# EsquemaPWM.net
KiCad netlist of a schematic drawn in EAGLE
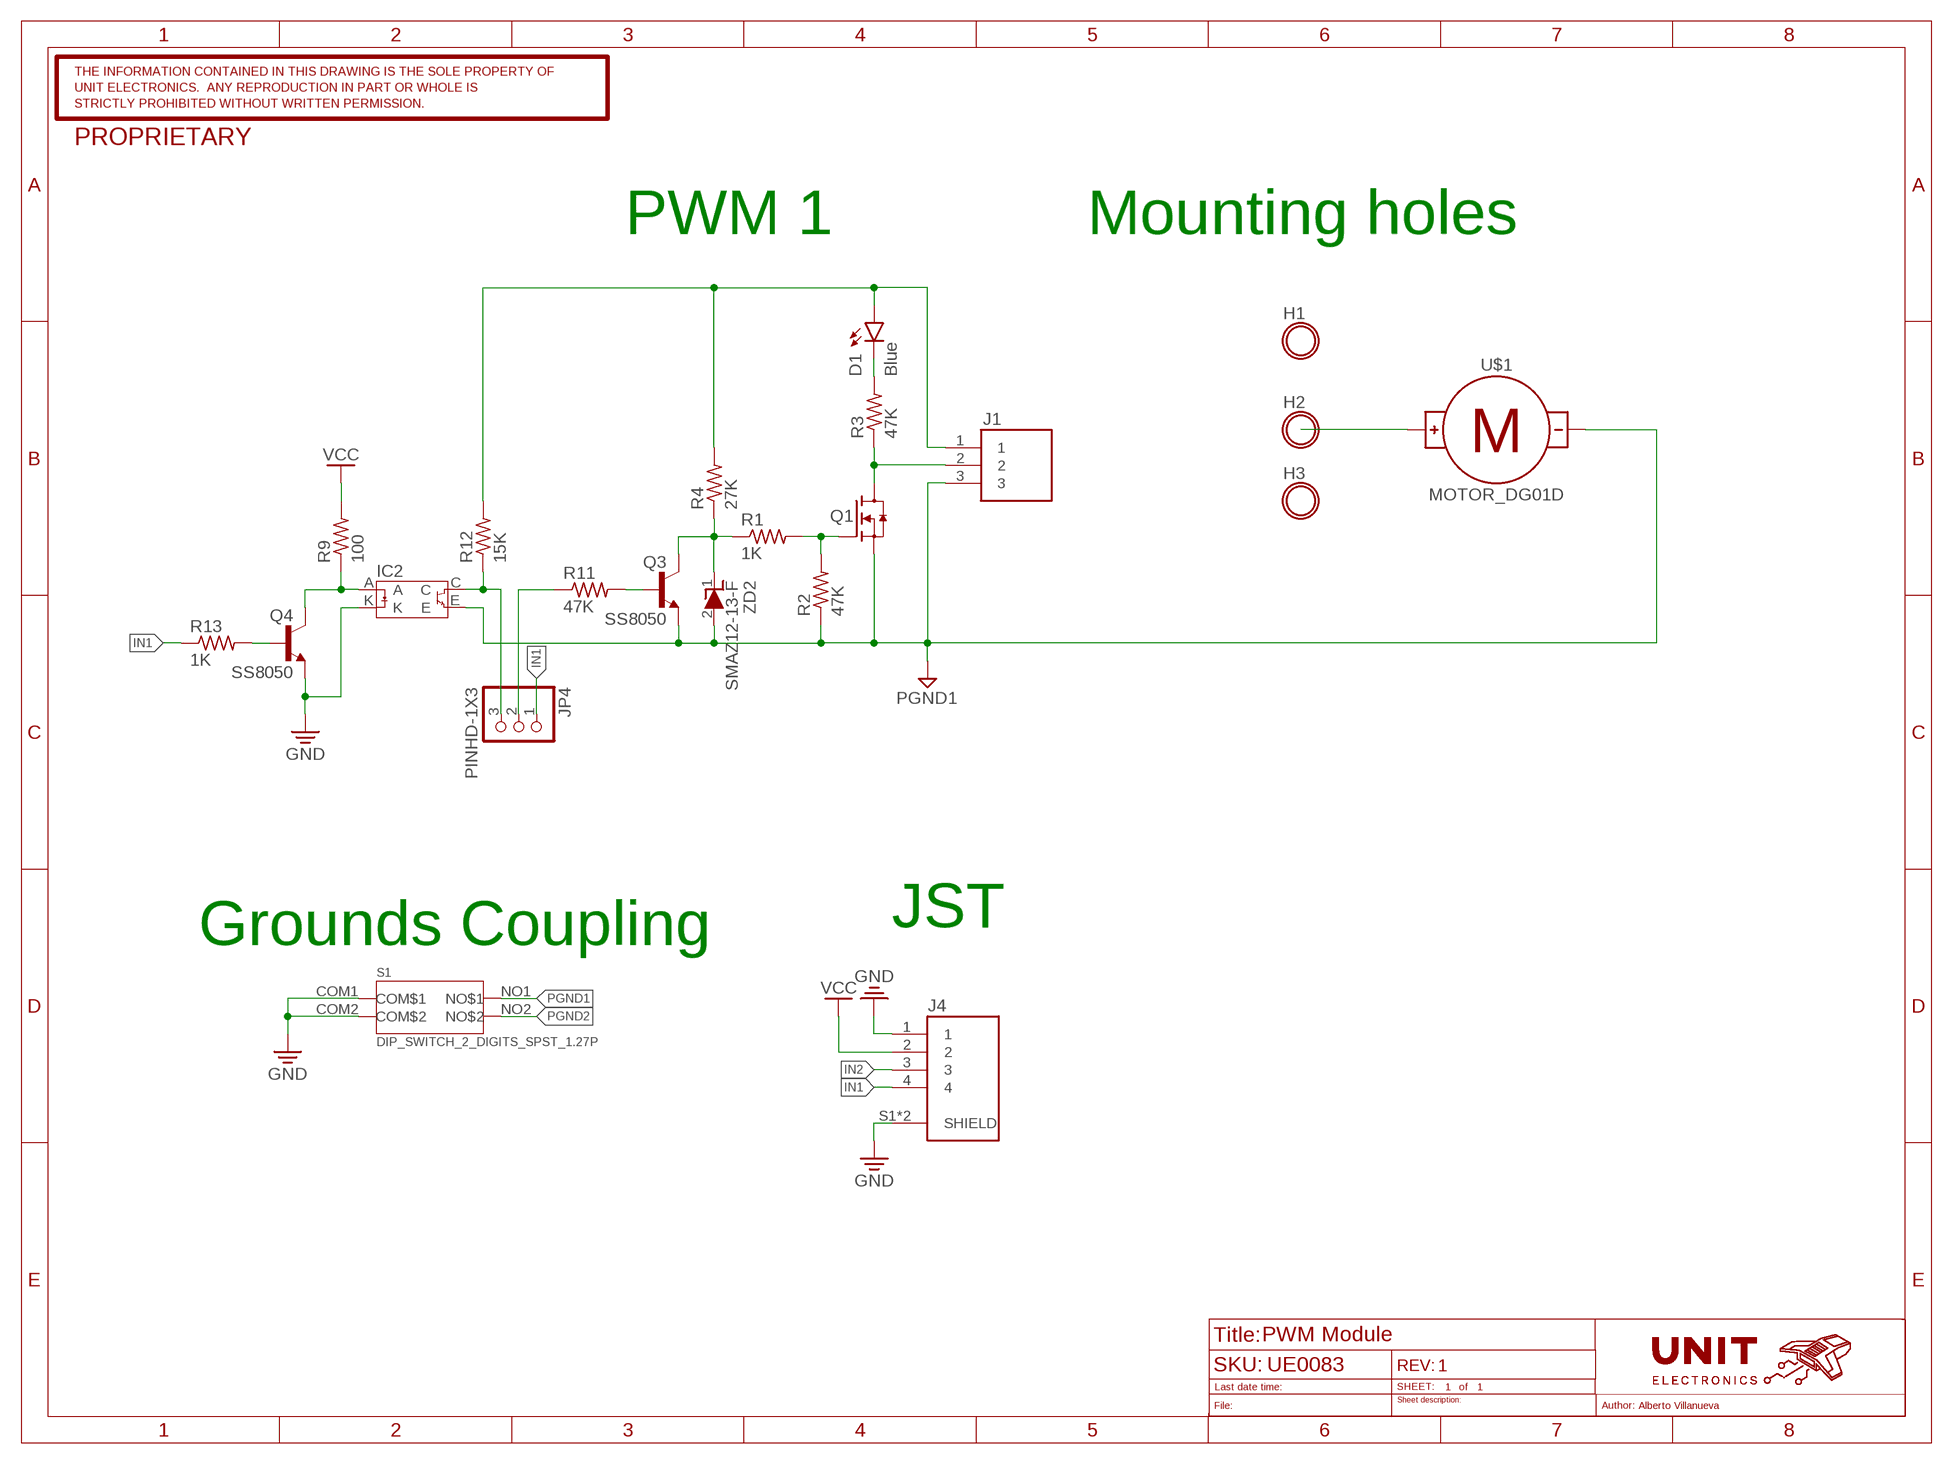
[diagram p0: schematic, sheet 1]

(export (version "E")
  (design (tool "Eeschema 10.0.6"))
  (components
    (comp (ref "D1")
      (value "Blue")
      (footprint "eagle-import:0402_D")
      (libsource (lib "eagle-import") (part "LED_SMD_0402"))
    )
    (comp (ref "H1")
      (value "HOLE_PADM2-THICK")
      (footprint "eagle-import:M2-THICK-OUTLINE")
      (libsource (lib "eagle-import") (part "HOLE_PADM2-THICK"))
    )
    (comp (ref "H2")
      (value "HOLE_PADM2-THICK")
      (footprint "eagle-import:M2-THICK-OUTLINE")
      (libsource (lib "eagle-import") (part "HOLE_PADM2-THICK"))
    )
    (comp (ref "H3")
      (value "HOLE_PADM2-THICK")
      (footprint "eagle-import:M2-THICK-OUTLINE")
      (libsource (lib "eagle-import") (part "HOLE_PADM2-THICK"))
    )
    (comp (ref "IC2")
      (value "EL3H7BTA-G")
      (footprint "eagle-import:SSOP-4")
      (fields
        (field (name "MANUFACTURER_PART_NUMBER") "EL3H7(B)(TA)-G")
        (field (name "VENDOR_PART_NUMBER") "C32565")
      )
      (libsource (lib "eagle-import") (part "EL3H7BTA-G"))
    )
    (comp (ref "J1")
      (value "BORNERA-KF301-3P")
      (footprint "eagle-import:KF301-5MM-3P")
      (fields
        (field (name "MANUFACTURER_PART_NUMBER") "KF301-5.0-3P ")
        (field (name "VENDOR_PART_NUMBER") "AR0315")
      )
      (libsource (lib "eagle-import") (part "BORNERA-KF301-3P"))
    )
    (comp (ref "J4")
      (value "QWIIC_JST_SR_4PINES_1MMBM04B-SRSS-TB(LF)(SN)")
      (footprint "eagle-import:SMD,P=1MM,4P,VERTICAL")
      (fields
        (field (name "MANUFACTURER_PART_NUMBER") "BM04B-SRSS-TB(LF)(SN) ")
        (field (name "VENDOR_PART_NUMBER") "AR2423")
      )
      (libsource (lib "eagle-import") (part "QWIIC_JST_SR_4PINES_1MMBM04B-SRSS-TB(LF)(SN)"))
    )
    (comp (ref "JP4")
      (value "PINHD-1X3")
      (footprint "eagle-import:1X3_PIN_HEADER_2.54MM_SILKSCREEN")
      (fields
        (field (name "MANUFACTURER_PART_NUMBER") "PZ2.54-UP1D-40A")
        (field (name "VENDOR_PART_NUMBER") "AR0164")
      )
      (libsource (lib "eagle-import") (part "PINHD-1X31X3_SILKSCREEN"))
    )
    (comp (ref "Q1")
      (value "HL4410")
      (footprint "eagle-import:SOP-8")
      (fields (field (name "MANUFACTURER_PART_NUMBER") "4410") (field (name "VENDOR_PART_NUMBER") "C7471105"))
      (libsource (lib "eagle-import") (part "HL4410"))
    )
    (comp (ref "Q3")
      (value "SS8050")
      (footprint "eagle-import:TRANS_SS8050-G")
      (fields (field (name "UNIT_PART_NUMBER") "AR2124"))
      (libsource (lib "eagle-import") (part "SS8050"))
    )
    (comp (ref "Q4")
      (value "SS8050")
      (footprint "eagle-import:TRANS_SS8050-G")
      (fields (field (name "UNIT_PART_NUMBER") "AR2124"))
      (libsource (lib "eagle-import") (part "SS8050"))
    )
    (comp (ref "R1")
      (value "1K")
      (footprint "eagle-import:0402_R")
      (libsource (lib "eagle-import") (part "RESISTOR_06030402_R"))
    )
    (comp (ref "R2")
      (value "47K")
      (footprint "eagle-import:0402_R")
      (libsource (lib "eagle-import") (part "RESISTOR_06030402_R"))
    )
    (comp (ref "R3")
      (value "47K")
      (footprint "eagle-import:0402_R")
      (libsource (lib "eagle-import") (part "RESISTOR_06030402_R"))
    )
    (comp (ref "R4")
      (value "27K")
      (footprint "eagle-import:0402_R")
      (libsource (lib "eagle-import") (part "RESISTOR_06030402_R"))
    )
    (comp (ref "R9")
      (value "100")
      (footprint "eagle-import:R1206")
      (libsource (lib "eagle-import") (part "RESISTOR_SMD1206_R"))
    )
    (comp (ref "R11")
      (value "47K")
      (footprint "eagle-import:0402_R")
      (libsource (lib "eagle-import") (part "RESISTOR_SMD0402_R"))
    )
    (comp (ref "R12")
      (value "15K")
      (footprint "eagle-import:0603_R")
      (libsource (lib "eagle-import") (part "RESISTOR_SMD"))
    )
    (comp (ref "R13")
      (value "1K")
      (footprint "eagle-import:0402_R")
      (libsource (lib "eagle-import") (part "RESISTOR_SMD0402_R"))
    )
    (comp (ref "S1")
      (value "DIP_SWITCH_2_DIGITS_SPST_1.27P")
      (footprint "eagle-import:SMD-4P,4.1X5.4MM")
      (fields
        (field (name "MANUFACTURER_PART_NUMBER") "DSHP02TSGET")
        (field (name "VENDOR_PART_NUMBER") "C40735")
      )
      (libsource (lib "eagle-import") (part "DIP_SWITCH_2_DIGITS_SPST_1.27P"))
    )
    (comp (ref "U$1")
      (value "MOTOR_DG01D")
      (footprint "eagle-import:DG01D")
      (libsource (lib "eagle-import") (part "MOTOR_DG01D"))
    )
    (comp (ref "ZD2")
      (value "SMAZ12-13-F")
      (footprint "eagle-import:SMA")
      (fields
        (field (name "MANUFACTURER_PART_NUMBER") "SMAZ12-13-F ")
        (field (name "VENDOR_PART_NUMBER") "AR2191")
      )
      (libsource (lib "eagle-import") (part "SMAZ12-13-F"))
    )
  )
  (nets
    (net (code "1") (name "GND") (class "Default")
      (node (ref "IC2") (pin "K") (pinfunction "K_K") (pintype "bidirectional"))
      (node (ref "J4") (pin "1") (pinfunction "1_1") (pintype "passive"))
      (node (ref "J4") (pin "S1") (pinfunction "SHIELD_S1") (pintype "passive"))
      (node (ref "J4") (pin "S2") (pinfunction "SHIELD_S2") (pintype "passive"))
      (node (ref "Q4") (pin "2") (pinfunction "E_2") (pintype "passive"))
      (node (ref "S1") (pin "COM1") (pinfunction "COM$1_COM1") (pintype "bidirectional"))
      (node (ref "S1") (pin "COM2") (pinfunction "COM$2_COM2") (pintype "bidirectional"))
    )
    (net (code "2") (name "IN1") (class "Default")
      (node (ref "J4") (pin "4") (pinfunction "4_4") (pintype "passive"))
      (node (ref "JP4") (pin "1") (pinfunction "1_1") (pintype "passive"))
      (node (ref "R13") (pin "1") (pinfunction "1_1") (pintype "passive"))
    )
    (net (code "3") (name "IN2") (class "Default")
      (node (ref "J4") (pin "3") (pinfunction "3_3") (pintype "passive"))
    )
    (net (code "4") (name "Net-(D1-PadA)") (class "Default")
      (node (ref "D1") (pin "A") (pinfunction "A_A") (pintype "passive"))
      (node (ref "J1") (pin "1") (pinfunction "1_1") (pintype "bidirectional"))
      (node (ref "R12") (pin "2") (pinfunction "2_2") (pintype "passive"))
      (node (ref "R4") (pin "2") (pinfunction "2_2") (pintype "passive"))
    )
    (net (code "5") (name "Net-(D1-PadC)") (class "Default")
      (node (ref "D1") (pin "C") (pinfunction "C_C") (pintype "passive"))
      (node (ref "R3") (pin "2") (pinfunction "2_2") (pintype "passive"))
    )
    (net (code "6") (name "Net-(IC2-PadC)") (class "Default")
      (node (ref "IC2") (pin "C") (pinfunction "C_C") (pintype "bidirectional"))
      (node (ref "JP4") (pin "3") (pinfunction "3_3") (pintype "passive"))
      (node (ref "R12") (pin "1") (pinfunction "1_1") (pintype "passive"))
    )
    (net (code "7") (name "Net-(J1-Pad2)") (class "Default")
      (node (ref "J1") (pin "2") (pinfunction "2_2") (pintype "bidirectional"))
      (node (ref "Q1") (pin "P$5") (pinfunction "D_P$5") (pintype "passive"))
      (node (ref "Q1") (pin "P$6") (pinfunction "D_P$6") (pintype "passive"))
      (node (ref "Q1") (pin "P$7") (pinfunction "D_P$7") (pintype "passive"))
      (node (ref "Q1") (pin "P$8") (pinfunction "D_P$8") (pintype "passive"))
      (node (ref "R3") (pin "1") (pinfunction "1_1") (pintype "passive"))
    )
    (net (code "8") (name "Net-(JP4-Pad2)") (class "Default")
      (node (ref "JP4") (pin "2") (pinfunction "2_2") (pintype "passive"))
      (node (ref "R11") (pin "1") (pinfunction "1_1") (pintype "passive"))
    )
    (net (code "9") (name "Net-(Q1-G)") (class "Default")
      (node (ref "Q1") (pin "P$4") (pinfunction "G_P$4") (pintype "passive"))
      (node (ref "R1") (pin "2") (pinfunction "2_2") (pintype "passive"))
      (node (ref "R2") (pin "2") (pinfunction "2_2") (pintype "passive"))
    )
    (net (code "10") (name "Net-(Q3-B)") (class "Default")
      (node (ref "Q3") (pin "1") (pinfunction "B_1") (pintype "passive"))
      (node (ref "R11") (pin "2") (pinfunction "2_2") (pintype "passive"))
    )
    (net (code "11") (name "Net-(Q3-C)") (class "Default")
      (node (ref "Q3") (pin "3") (pinfunction "C_3") (pintype "passive"))
      (node (ref "R1") (pin "1") (pinfunction "1_1") (pintype "passive"))
      (node (ref "R4") (pin "1") (pinfunction "1_1") (pintype "passive"))
      (node (ref "ZD2") (pin "1") (pinfunction "K_1") (pintype "bidirectional"))
    )
    (net (code "12") (name "Net-(Q4-B)") (class "Default")
      (node (ref "Q4") (pin "1") (pinfunction "B_1") (pintype "passive"))
      (node (ref "R13") (pin "2") (pinfunction "2_2") (pintype "passive"))
    )
    (net (code "13") (name "Net-(Q4-C)") (class "Default")
      (node (ref "IC2") (pin "A") (pinfunction "A_A") (pintype "bidirectional"))
      (node (ref "Q4") (pin "3") (pinfunction "C_3") (pintype "passive"))
      (node (ref "R9") (pin "1") (pinfunction "1_1") (pintype "passive"))
    )
    (net (code "14") (name "PGND1") (class "Default")
      (node (ref "IC2") (pin "E") (pinfunction "E_E") (pintype "bidirectional"))
      (node (ref "J1") (pin "3") (pinfunction "3_3") (pintype "bidirectional"))
      (node (ref "Q1") (pin "P$1") (pinfunction "S_P$1") (pintype "passive"))
      (node (ref "Q1") (pin "P$2") (pinfunction "S_P$2") (pintype "passive"))
      (node (ref "Q1") (pin "P$3") (pinfunction "S_P$3") (pintype "passive"))
      (node (ref "Q3") (pin "2") (pinfunction "E_2") (pintype "passive"))
      (node (ref "R2") (pin "1") (pinfunction "1_1") (pintype "passive"))
      (node (ref "S1") (pin "NO1") (pinfunction "NO$1_NO1") (pintype "bidirectional"))
      (node (ref "U$1") (pin "-") (pinfunction "-_-") (pintype "passive"))
      (node (ref "ZD2") (pin "2") (pinfunction "A_2") (pintype "bidirectional"))
    )
    (net (code "15") (name "PGND2") (class "Default")
      (node (ref "S1") (pin "NO2") (pinfunction "NO$2_NO2") (pintype "bidirectional"))
    )
    (net (code "16") (name "VCC") (class "Default")
      (node (ref "J4") (pin "2") (pinfunction "2_2") (pintype "passive"))
      (node (ref "R9") (pin "2") (pinfunction "2_2") (pintype "passive"))
    )
    (net (code "17") (name "unconnected-(U$1-Pad+)") (class "Default")
      (node (ref "U$1") (pin "+") (pinfunction "+_+") (pintype "passive"))
    )
  )
)
